# ProPrj_Iris_Zero_2026-02-21.net
KiCad netlist of a schematic drawn in EasyEDA Pro
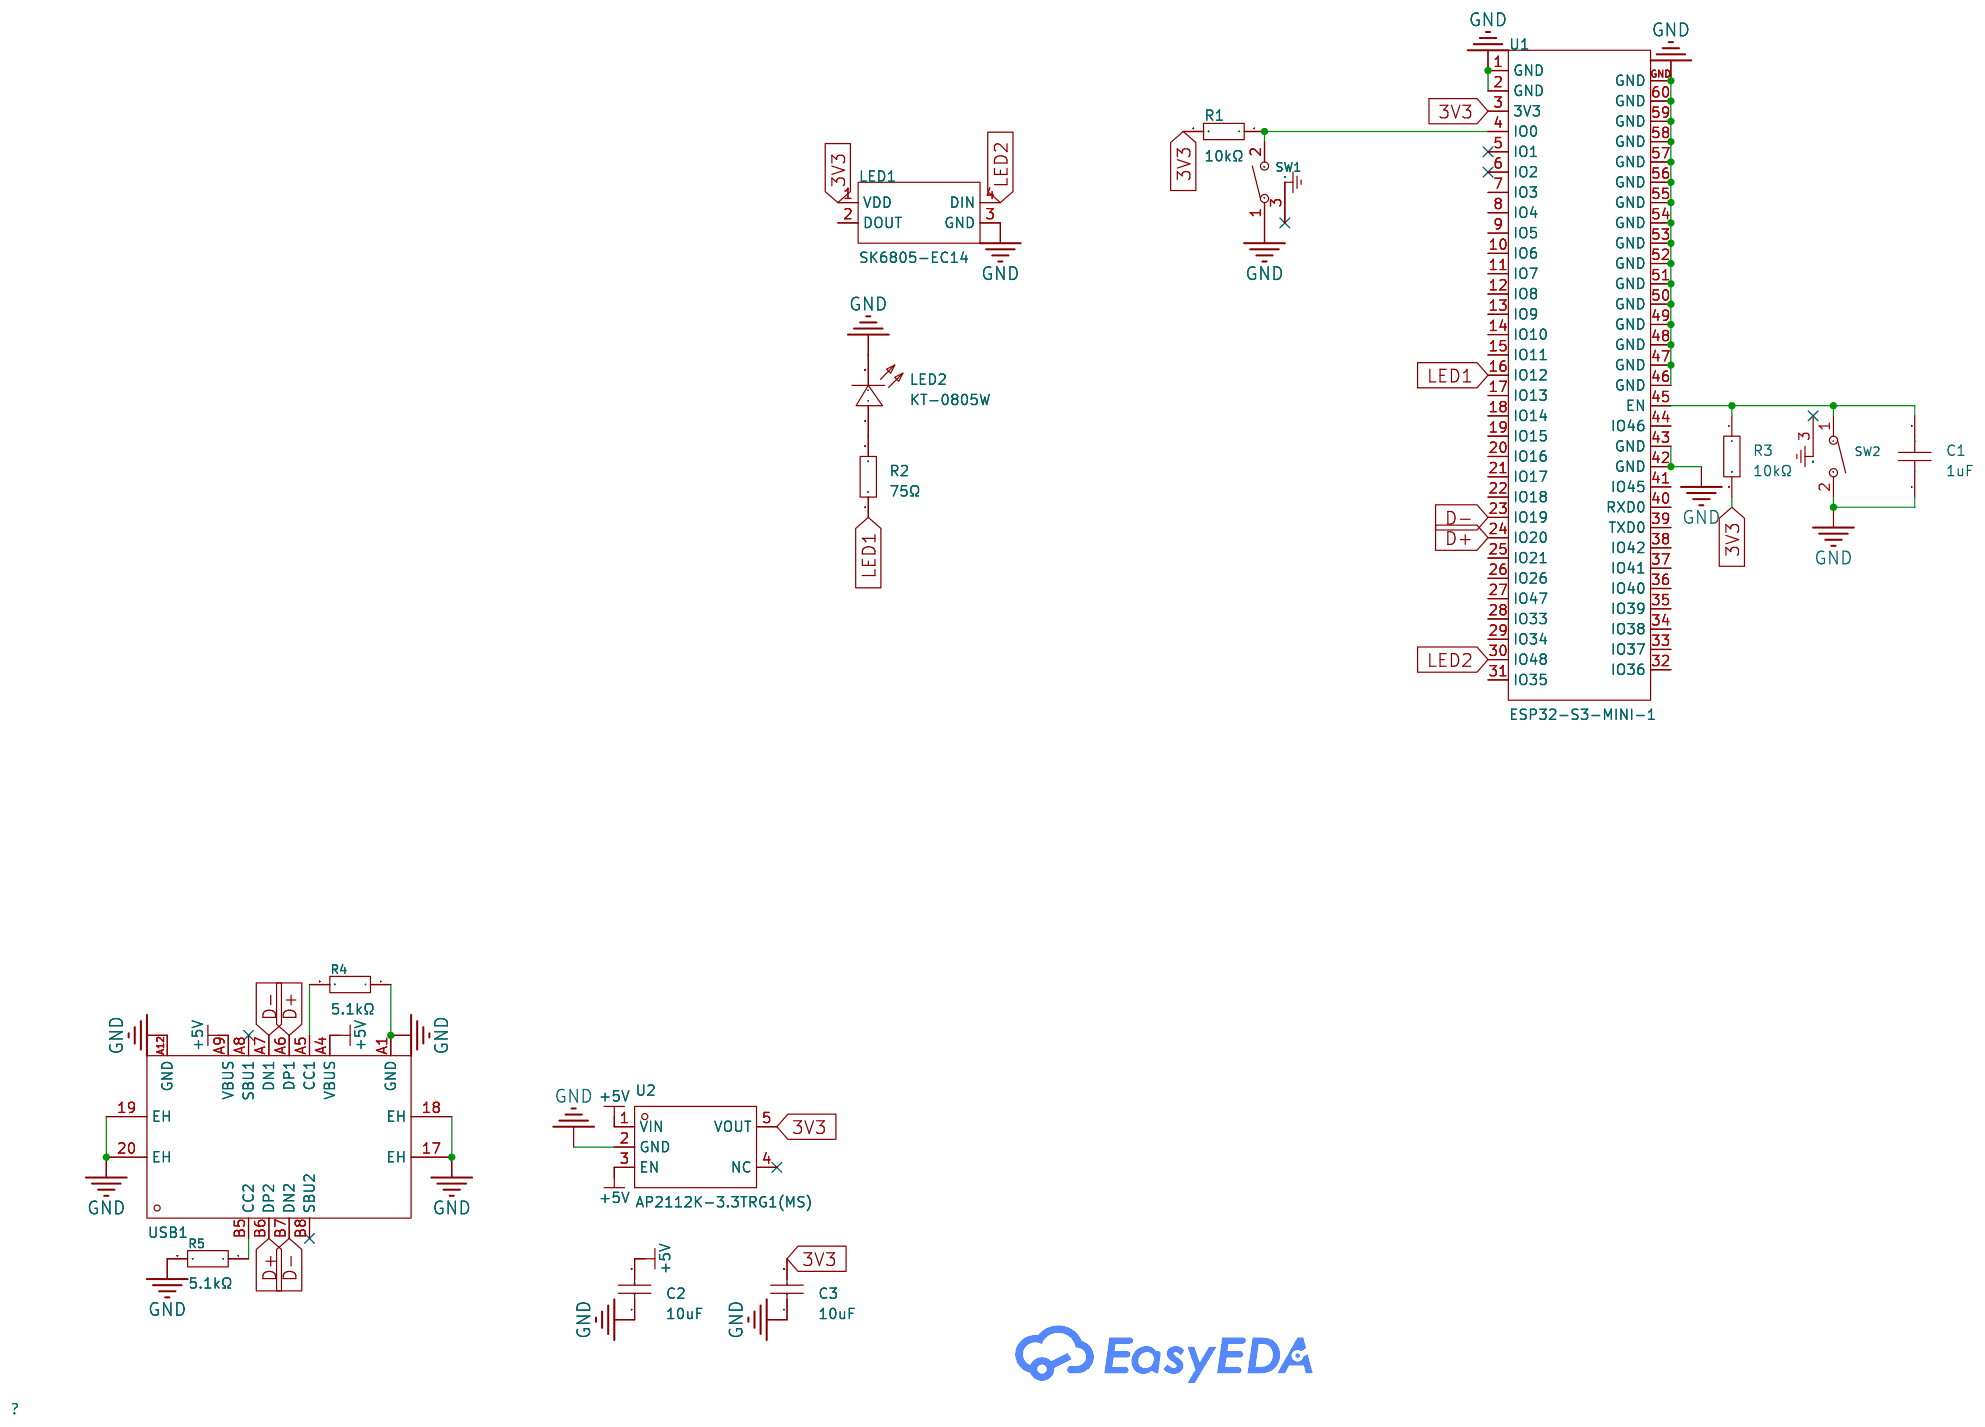
[diagram p0: schematic sheet]

(export (version "E")
  (design (tool "Eeschema 10.0.6"))
  (components
    (comp (ref "C1")
      (value "1uF")
      (footprint "easyedapro:C0402")
      (description "Capacitance:1uF Tolerance:±10% Tolerance:±10% Voltage Rating:25V Temperature Coefficient:X5R")
      (fields
        (field (name "Manufacturer Part") "CL05A105KA5NQNC")
        (field (name "Manufacturer") "SAMSUNG(三星)")
      )
      (libsource (lib "easyedapro") (part "CL05A105KA5NQNC"))
    )
    (comp (ref "C2")
      (value "10uF")
      (footprint "easyedapro:C0402")
      (description "Capacitance:10uF Tolerance:±20% Tolerance:±20% Voltage Rating:6.3V Temperature Coefficient:X5R")
      (fields
        (field (name "Manufacturer Part") "CL05A106MQ5NUNC")
        (field (name "Manufacturer") "SAMSUNG(三星)")
      )
      (libsource (lib "easyedapro") (part "CL05A106MQ5NUNC"))
    )
    (comp (ref "C3")
      (value "10uF")
      (footprint "easyedapro:C0402")
      (description "Capacitance:10uF Tolerance:±20% Tolerance:±20% Voltage Rating:6.3V Temperature Coefficient:X5R")
      (fields
        (field (name "Manufacturer Part") "CL05A106MQ5NUNC")
        (field (name "Manufacturer") "SAMSUNG(三星)")
      )
      (libsource (lib "easyedapro") (part "CL05A106MQ5NUNC"))
    )
    (comp (ref "LED1")
      (value "SK6805-EC14")
      (footprint "easyedapro:LED-SMD_4P-L1.4-W1.4-TL")
      (fields (field (name "Manufacturer") "欧思科光电"))
      (libsource (lib "easyedapro") (part "SK6805-EC14_C2909055"))
    )
    (comp (ref "LED2")
      (value "KT-0805W")
      (footprint "easyedapro:LED0805-R-RD")
      (fields (field (name "Manufacturer") "KENTO"))
      (libsource (lib "easyedapro") (part "whiteLEDSMD"))
    )
    (comp (ref "R1")
      (value "10kΩ")
      (footprint "easyedapro:R0402")
      (fields
        (field (name "Manufacturer Part") "0402WGF1002TCE")
        (field (name "Manufacturer") "UNI-ROYAL(厚声)")
      )
      (libsource (lib "easyedapro") (part "0402WGF1002TCE"))
    )
    (comp (ref "R2")
      (value "75Ω")
      (footprint "easyedapro:R0402")
      (fields
        (field (name "Manufacturer Part") "0402WGF750JTCE")
        (field (name "Manufacturer") "UNI-ROYAL(厚声)")
      )
      (libsource (lib "easyedapro") (part "0402WGF750JTCE"))
    )
    (comp (ref "R3")
      (value "10kΩ")
      (footprint "easyedapro:R0402")
      (fields
        (field (name "Manufacturer Part") "0402WGF1002TCE")
        (field (name "Manufacturer") "UNI-ROYAL(厚声)")
      )
      (libsource (lib "easyedapro") (part "0402WGF1002TCE"))
    )
    (comp (ref "R4")
      (value "5.1kΩ")
      (footprint "easyedapro:R0402")
      (fields
        (field (name "Manufacturer Part") "0402WGF5101TCE")
        (field (name "Manufacturer") "UNI-ROYAL(厚声)")
      )
      (libsource (lib "easyedapro") (part "0402WGF5101TCE"))
    )
    (comp (ref "R5")
      (value "5.1kΩ")
      (footprint "easyedapro:R0402")
      (fields
        (field (name "Manufacturer Part") "0402WGF5101TCE")
        (field (name "Manufacturer") "UNI-ROYAL(厚声)")
      )
      (libsource (lib "easyedapro") (part "0402WGF5101TCE"))
    )
    (comp (ref "SW1")
      (value "SKTDLHE010")
      (footprint "easyedapro:KEY-SMD_SKTDLHE010")
      (description "Circuit:SPST Actuator Style:Rectangle button Mounting Style:卧贴 With Lamp:- Mechanical Life:-")
      (fields (field (name "Manufacturer") "ALPSALPINE(阿尔卑斯阿尔派)"))
      (libsource (lib "easyedapro") (part "SKTDLHE010"))
    )
    (comp (ref "SW2")
      (value "SKTDLHE010")
      (footprint "easyedapro:KEY-SMD_SKTDLHE010")
      (description "Circuit:SPST Actuator Style:Rectangle button Mounting Style:卧贴 With Lamp:- Mechanical Life:-")
      (fields (field (name "Manufacturer") "ALPSALPINE(阿尔卑斯阿尔派)"))
      (libsource (lib "easyedapro") (part "SKTDLHE010"))
    )
    (comp (ref "U1")
      (value "ESP32-S3-MINI-1")
      (footprint "easyedapro:BULETM-SMD_ESP32-S3-MINI-1-N8")
      (libsource (lib "easyedapro") (part "ESP32-S3-MINI-1"))
    )
    (comp (ref "U2")
      (value "AP2112K-3.3TRG1(MS)")
      (footprint "easyedapro:SOT-23-5_L2.9-W1.6-P0.95-LS2.7-BR")
      (fields (field (name "Manufacturer") "MSKSEMI(美森科)"))
      (libsource (lib "easyedapro") (part "AP2112K-3.3TRG1(MS)"))
    )
    (comp (ref "USB1")
      (value "TYPE-C 16P QTGM027")
      (footprint "easyedapro:USB-C-SMD_TYPE-C-16P-QTGM027")
      (fields (field (name "Manufacturer") "SHOU HAN(首韩)"))
      (libsource (lib "easyedapro") (part "TYPE-C 16P QTGM027"))
    )
  )
  (nets
    (net (code "1") (name "+5V") (class "Default")
      (node (ref "C2") (pin "2") (pinfunction "2_2") (pintype "input"))
      (node (ref "U2") (pin "1") (pinfunction "VIN_1") (pintype "unspecified"))
      (node (ref "U2") (pin "3") (pinfunction "EN_3") (pintype "unspecified"))
      (node (ref "USB1") (pin "A4") (pinfunction "VBUS_A4") (pintype "unspecified"))
      (node (ref "USB1") (pin "A9") (pinfunction "VBUS_A9") (pintype "unspecified"))
    )
    (net (code "2") (name "3V3") (class "Default")
      (node (ref "C3") (pin "2") (pinfunction "2_2") (pintype "input"))
      (node (ref "LED1") (pin "1") (pinfunction "VDD_1") (pintype "unspecified"))
      (node (ref "R1") (pin "2") (pinfunction "2_2") (pintype "input"))
      (node (ref "R3") (pin "2") (pinfunction "2_2") (pintype "input"))
      (node (ref "U1") (pin "3") (pinfunction "3V3_3") (pintype "unspecified"))
      (node (ref "U2") (pin "5") (pinfunction "VOUT_5") (pintype "unspecified"))
    )
    (net (code "3") (name "D+") (class "Default")
      (node (ref "U1") (pin "24") (pinfunction "IO20_24") (pintype "unspecified"))
      (node (ref "USB1") (pin "A6") (pinfunction "DP1_A6") (pintype "unspecified"))
      (node (ref "USB1") (pin "B6") (pinfunction "DP2_B6") (pintype "unspecified"))
    )
    (net (code "4") (name "D-") (class "Default")
      (node (ref "U1") (pin "23") (pinfunction "IO19_23") (pintype "unspecified"))
      (node (ref "USB1") (pin "A7") (pinfunction "DN1_A7") (pintype "unspecified"))
      (node (ref "USB1") (pin "B7") (pinfunction "DN2_B7") (pintype "unspecified"))
    )
    (net (code "5") (name "GND") (class "Default")
      (node (ref "C1") (pin "1") (pinfunction "1_1") (pintype "unspecified"))
      (node (ref "C2") (pin "1") (pinfunction "1_1") (pintype "input"))
      (node (ref "C3") (pin "1") (pinfunction "1_1") (pintype "input"))
      (node (ref "LED1") (pin "3") (pinfunction "GND_3") (pintype "unspecified"))
      (node (ref "LED2") (pin "2") (pinfunction "K_2") (pintype "unspecified"))
      (node (ref "R4") (pin "1") (pinfunction "1_1") (pintype "input"))
      (node (ref "R5") (pin "2") (pinfunction "2_2") (pintype "input"))
      (node (ref "SW1") (pin "1") (pinfunction "1_1") (pintype "input"))
      (node (ref "SW2") (pin "2") (pinfunction "2_2") (pintype "input"))
      (node (ref "U1") (pin "1") (pinfunction "GND_1") (pintype "unspecified"))
      (node (ref "U1") (pin "2") (pinfunction "GND_2") (pintype "unspecified"))
      (node (ref "U1") (pin "42") (pinfunction "GND_42") (pintype "unspecified"))
      (node (ref "U1") (pin "43") (pinfunction "GND_43") (pintype "unspecified"))
      (node (ref "U1") (pin "46") (pinfunction "GND_46") (pintype "unspecified"))
      (node (ref "U1") (pin "47") (pinfunction "GND_47") (pintype "unspecified"))
      (node (ref "U1") (pin "48") (pinfunction "GND_48") (pintype "unspecified"))
      (node (ref "U1") (pin "49") (pinfunction "GND_49") (pintype "unspecified"))
      (node (ref "U1") (pin "50") (pinfunction "GND_50") (pintype "unspecified"))
      (node (ref "U1") (pin "51") (pinfunction "GND_51") (pintype "unspecified"))
      (node (ref "U1") (pin "52") (pinfunction "GND_52") (pintype "unspecified"))
      (node (ref "U1") (pin "53") (pinfunction "GND_53") (pintype "unspecified"))
      (node (ref "U1") (pin "54") (pinfunction "GND_54") (pintype "unspecified"))
      (node (ref "U1") (pin "55") (pinfunction "GND_55") (pintype "unspecified"))
      (node (ref "U1") (pin "56") (pinfunction "GND_56") (pintype "unspecified"))
      (node (ref "U1") (pin "57") (pinfunction "GND_57") (pintype "unspecified"))
      (node (ref "U1") (pin "58") (pinfunction "GND_58") (pintype "unspecified"))
      (node (ref "U1") (pin "59") (pinfunction "GND_59") (pintype "unspecified"))
      (node (ref "U1") (pin "60") (pinfunction "GND_60") (pintype "unspecified"))
      (node (ref "U1") (pin "GND") (pinfunction "GND_GND") (pintype "unspecified"))
      (node (ref "U2") (pin "2") (pinfunction "GND_2") (pintype "unspecified"))
      (node (ref "USB1") (pin "17") (pinfunction "EH_17") (pintype "unspecified"))
      (node (ref "USB1") (pin "18") (pinfunction "EH_18") (pintype "unspecified"))
      (node (ref "USB1") (pin "19") (pinfunction "EH_19") (pintype "unspecified"))
      (node (ref "USB1") (pin "20") (pinfunction "EH_20") (pintype "unspecified"))
      (node (ref "USB1") (pin "A1") (pinfunction "GND_A1") (pintype "unspecified"))
      (node (ref "USB1") (pin "A12") (pinfunction "GND_A12") (pintype "unspecified"))
    )
    (net (code "6") (name "LED1") (class "Default")
      (node (ref "R2") (pin "1") (pinfunction "1_1") (pintype "input"))
      (node (ref "U1") (pin "16") (pinfunction "IO12_16") (pintype "unspecified"))
    )
    (net (code "7") (name "LED2") (class "Default")
      (node (ref "LED1") (pin "4") (pinfunction "DIN_4") (pintype "unspecified"))
      (node (ref "U1") (pin "30") (pinfunction "IO48_30") (pintype "unspecified"))
    )
    (net (code "8") (name "Net-(LED2-A)") (class "Default")
      (node (ref "LED2") (pin "1") (pinfunction "A_1") (pintype "unspecified"))
      (node (ref "R2") (pin "2") (pinfunction "2_2") (pintype "input"))
    )
    (net (code "9") (name "Net-(U1-EN)") (class "Default")
      (node (ref "C1") (pin "2") (pinfunction "2_2") (pintype "unspecified"))
      (node (ref "R3") (pin "1") (pinfunction "1_1") (pintype "input"))
      (node (ref "SW2") (pin "1") (pinfunction "1_1") (pintype "input"))
      (node (ref "U1") (pin "45") (pinfunction "EN_45") (pintype "unspecified"))
    )
    (net (code "10") (name "Net-(U1-IO0)") (class "Default")
      (node (ref "R1") (pin "1") (pinfunction "1_1") (pintype "input"))
      (node (ref "SW1") (pin "2") (pinfunction "2_2") (pintype "input"))
      (node (ref "U1") (pin "4") (pinfunction "IO0_4") (pintype "unspecified"))
    )
    (net (code "11") (name "Net-(USB1-CC1)") (class "Default")
      (node (ref "R4") (pin "2") (pinfunction "2_2") (pintype "input"))
      (node (ref "USB1") (pin "A5") (pinfunction "CC1_A5") (pintype "unspecified"))
    )
    (net (code "12") (name "Net-(USB1-CC2)") (class "Default")
      (node (ref "R5") (pin "1") (pinfunction "1_1") (pintype "input"))
      (node (ref "USB1") (pin "B5") (pinfunction "CC2_B5") (pintype "unspecified"))
    )
    (net (code "13") (name "unconnected-(LED1-DOUT-Pad2)") (class "Default")
      (node (ref "LED1") (pin "2") (pinfunction "DOUT_2") (pintype "unspecified"))
    )
    (net (code "14") (name "unconnected-(SW1-GND-Pad3)") (class "Default")
      (node (ref "SW1") (pin "3") (pinfunction "GND_3") (pintype "input+no_connect"))
    )
    (net (code "15") (name "unconnected-(SW2-GND-Pad3)") (class "Default")
      (node (ref "SW2") (pin "3") (pinfunction "GND_3") (pintype "input+no_connect"))
    )
    (net (code "16") (name "unconnected-(U1-IO1-Pad5)") (class "Default")
      (node (ref "U1") (pin "5") (pinfunction "IO1_5") (pintype "unspecified+no_connect"))
    )
    (net (code "17") (name "unconnected-(U1-IO2-Pad6)") (class "Default")
      (node (ref "U1") (pin "6") (pinfunction "IO2_6") (pintype "unspecified+no_connect"))
    )
    (net (code "18") (name "unconnected-(U1-IO3-Pad7)") (class "Default")
      (node (ref "U1") (pin "7") (pinfunction "IO3_7") (pintype "unspecified"))
    )
    (net (code "19") (name "unconnected-(U1-IO4-Pad8)") (class "Default")
      (node (ref "U1") (pin "8") (pinfunction "IO4_8") (pintype "unspecified"))
    )
    (net (code "20") (name "unconnected-(U1-IO5-Pad9)") (class "Default")
      (node (ref "U1") (pin "9") (pinfunction "IO5_9") (pintype "unspecified"))
    )
    (net (code "21") (name "unconnected-(U1-IO6-Pad10)") (class "Default")
      (node (ref "U1") (pin "10") (pinfunction "IO6_10") (pintype "unspecified"))
    )
    (net (code "22") (name "unconnected-(U1-IO7-Pad11)") (class "Default")
      (node (ref "U1") (pin "11") (pinfunction "IO7_11") (pintype "unspecified"))
    )
    (net (code "23") (name "unconnected-(U1-IO8-Pad12)") (class "Default")
      (node (ref "U1") (pin "12") (pinfunction "IO8_12") (pintype "unspecified"))
    )
    (net (code "24") (name "unconnected-(U1-IO9-Pad13)") (class "Default")
      (node (ref "U1") (pin "13") (pinfunction "IO9_13") (pintype "unspecified"))
    )
    (net (code "25") (name "unconnected-(U1-IO10-Pad14)") (class "Default")
      (node (ref "U1") (pin "14") (pinfunction "IO10_14") (pintype "unspecified"))
    )
    (net (code "26") (name "unconnected-(U1-IO11-Pad15)") (class "Default")
      (node (ref "U1") (pin "15") (pinfunction "IO11_15") (pintype "unspecified"))
    )
    (net (code "27") (name "unconnected-(U1-IO13-Pad17)") (class "Default")
      (node (ref "U1") (pin "17") (pinfunction "IO13_17") (pintype "unspecified"))
    )
    (net (code "28") (name "unconnected-(U1-IO14-Pad18)") (class "Default")
      (node (ref "U1") (pin "18") (pinfunction "IO14_18") (pintype "unspecified"))
    )
    (net (code "29") (name "unconnected-(U1-IO15-Pad19)") (class "Default")
      (node (ref "U1") (pin "19") (pinfunction "IO15_19") (pintype "unspecified"))
    )
    (net (code "30") (name "unconnected-(U1-IO16-Pad20)") (class "Default")
      (node (ref "U1") (pin "20") (pinfunction "IO16_20") (pintype "unspecified"))
    )
    (net (code "31") (name "unconnected-(U1-IO17-Pad21)") (class "Default")
      (node (ref "U1") (pin "21") (pinfunction "IO17_21") (pintype "unspecified"))
    )
    (net (code "32") (name "unconnected-(U1-IO18-Pad22)") (class "Default")
      (node (ref "U1") (pin "22") (pinfunction "IO18_22") (pintype "unspecified"))
    )
    (net (code "33") (name "unconnected-(U1-IO21-Pad25)") (class "Default")
      (node (ref "U1") (pin "25") (pinfunction "IO21_25") (pintype "unspecified"))
    )
    (net (code "34") (name "unconnected-(U1-IO26-Pad26)") (class "Default")
      (node (ref "U1") (pin "26") (pinfunction "IO26_26") (pintype "unspecified"))
    )
    (net (code "35") (name "unconnected-(U1-IO33-Pad28)") (class "Default")
      (node (ref "U1") (pin "28") (pinfunction "IO33_28") (pintype "unspecified"))
    )
    (net (code "36") (name "unconnected-(U1-IO34-Pad29)") (class "Default")
      (node (ref "U1") (pin "29") (pinfunction "IO34_29") (pintype "unspecified"))
    )
    (net (code "37") (name "unconnected-(U1-IO35-Pad31)") (class "Default")
      (node (ref "U1") (pin "31") (pinfunction "IO35_31") (pintype "unspecified"))
    )
    (net (code "38") (name "unconnected-(U1-IO36-Pad32)") (class "Default")
      (node (ref "U1") (pin "32") (pinfunction "IO36_32") (pintype "unspecified"))
    )
    (net (code "39") (name "unconnected-(U1-IO37-Pad33)") (class "Default")
      (node (ref "U1") (pin "33") (pinfunction "IO37_33") (pintype "unspecified"))
    )
    (net (code "40") (name "unconnected-(U1-IO38-Pad34)") (class "Default")
      (node (ref "U1") (pin "34") (pinfunction "IO38_34") (pintype "unspecified"))
    )
    (net (code "41") (name "unconnected-(U1-IO39-Pad35)") (class "Default")
      (node (ref "U1") (pin "35") (pinfunction "IO39_35") (pintype "unspecified"))
    )
    (net (code "42") (name "unconnected-(U1-IO40-Pad36)") (class "Default")
      (node (ref "U1") (pin "36") (pinfunction "IO40_36") (pintype "unspecified"))
    )
    (net (code "43") (name "unconnected-(U1-IO41-Pad37)") (class "Default")
      (node (ref "U1") (pin "37") (pinfunction "IO41_37") (pintype "unspecified"))
    )
    (net (code "44") (name "unconnected-(U1-IO42-Pad38)") (class "Default")
      (node (ref "U1") (pin "38") (pinfunction "IO42_38") (pintype "unspecified"))
    )
    (net (code "45") (name "unconnected-(U1-IO45-Pad41)") (class "Default")
      (node (ref "U1") (pin "41") (pinfunction "IO45_41") (pintype "unspecified"))
    )
    (net (code "46") (name "unconnected-(U1-IO46-Pad44)") (class "Default")
      (node (ref "U1") (pin "44") (pinfunction "IO46_44") (pintype "unspecified"))
    )
    (net (code "47") (name "unconnected-(U1-IO47-Pad27)") (class "Default")
      (node (ref "U1") (pin "27") (pinfunction "IO47_27") (pintype "unspecified"))
    )
    (net (code "48") (name "unconnected-(U1-RXD0-Pad40)") (class "Default")
      (node (ref "U1") (pin "40") (pinfunction "RXD0_40") (pintype "unspecified"))
    )
    (net (code "49") (name "unconnected-(U1-TXD0-Pad39)") (class "Default")
      (node (ref "U1") (pin "39") (pinfunction "TXD0_39") (pintype "unspecified"))
    )
    (net (code "50") (name "unconnected-(U2-NC-Pad4)") (class "Default")
      (node (ref "U2") (pin "4") (pinfunction "NC_4") (pintype "unspecified+no_connect"))
    )
    (net (code "51") (name "unconnected-(USB1-SBU1-PadA8)") (class "Default")
      (node (ref "USB1") (pin "A8") (pinfunction "SBU1_A8") (pintype "unspecified+no_connect"))
    )
    (net (code "52") (name "unconnected-(USB1-SBU2-PadB8)") (class "Default")
      (node (ref "USB1") (pin "B8") (pinfunction "SBU2_B8") (pintype "unspecified+no_connect"))
    )
  )
)
